# fuenteRegulada.net
KiCad netlist of a schematic drawn in Altium Designer
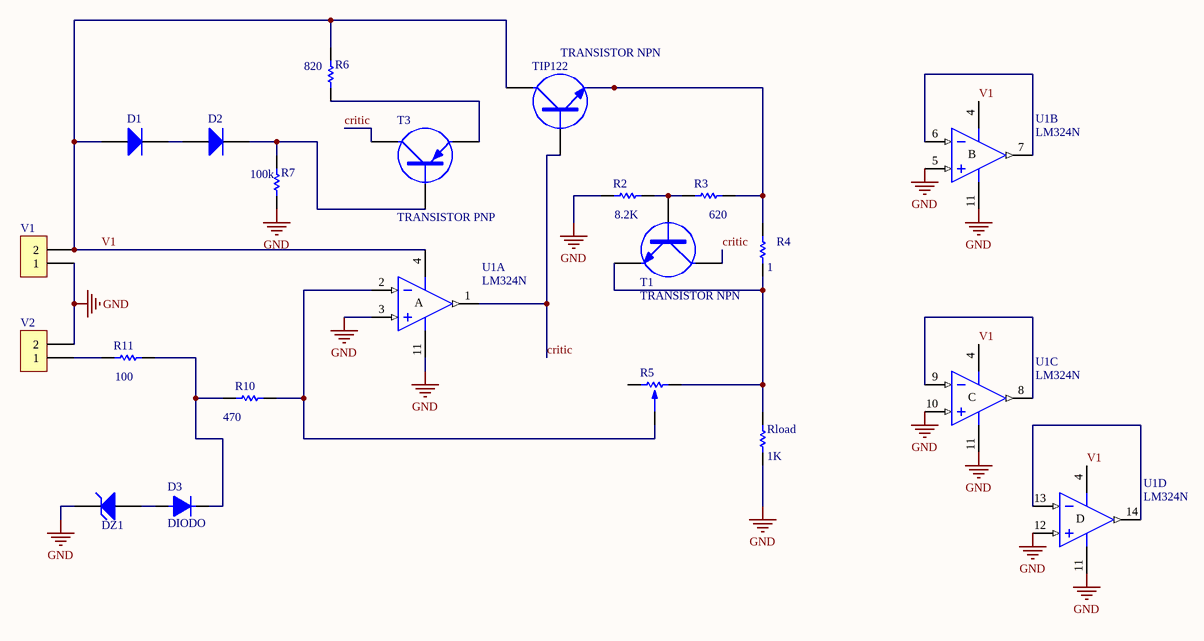
[diagram p0: fuenteRegulada.SchDoc]

(export (version "E")
  (design (tool "Eeschema 10.0.6"))
  (components
    (comp (ref "D1")
      (value "Diode 1N914")
      (footprint "DO-35")
      (description "High Conductance Fast Diode")
      (fields (field (name "PUBLISHER") "Altium Limited"))
      (libsource (lib "Miscellaneous Devices") (part "Diode 1N914"))
    )
    (comp (ref "D2")
      (value "Diode 1N914")
      (footprint "DO-35")
      (description "High Conductance Fast Diode")
      (fields (field (name "PUBLISHER") "Altium Limited"))
      (libsource (lib "Miscellaneous Devices") (part "Diode 1N914"))
    )
    (comp (ref "D3") (value "DIODO") (footprint "DO41") (libsource (lib "LIBEBAL") (part "DIODO")))
    (comp (ref "DZ1")
      (value "D Zener")
      (footprint "DIODE-0.7")
      (description "Zener Diode")
      (fields (field (name "PUBLISHER") "Altium Limited"))
      (libsource (lib "Miscellaneous Devices") (part "D Zener"))
    )
    (comp (ref "R2")
      (value "8.2K")
      (footprint "AXIAL-0.3")
      (description "Resistor")
      (fields (field (name "Comment") "Res1") (field (name "PUBLISHER") "Altium Limited"))
      (libsource (lib "Miscellaneous Devices") (part "Res1"))
    )
    (comp (ref "R3")
      (value "620")
      (footprint "AXIAL-0.3")
      (description "Resistor")
      (fields (field (name "Comment") "Res1") (field (name "PUBLISHER") "Altium Limited"))
      (libsource (lib "Miscellaneous Devices") (part "Res1"))
    )
    (comp (ref "R4")
      (value "1")
      (footprint "AXIAL-0.3")
      (description "Resistor")
      (fields (field (name "Comment") "Res1") (field (name "PUBLISHER") "Altium Limited"))
      (libsource (lib "Miscellaneous Devices") (part "Res1"))
    )
    (comp (ref "R5") (value "PRESET") (footprint "PRESET V") (libsource (lib "LIBEBAL") (part "PRESET")))
    (comp (ref "R6")
      (value "820")
      (footprint "AXIAL-0.3")
      (description "Resistor")
      (fields (field (name "Comment") "Res1") (field (name "PUBLISHER") "Altium Limited"))
      (libsource (lib "Miscellaneous Devices") (part "Res1"))
    )
    (comp (ref "R7")
      (value "100k")
      (footprint "AXIAL-0.3")
      (description "Resistor")
      (fields (field (name "Comment") "Res1") (field (name "PUBLISHER") "Altium Limited"))
      (libsource (lib "Miscellaneous Devices") (part "Res1"))
    )
    (comp (ref "R10")
      (value "470")
      (footprint "AXIAL-0.3")
      (description "Resistor")
      (fields (field (name "Comment") "Res1") (field (name "PUBLISHER") "Altium Limited"))
      (libsource (lib "Miscellaneous Devices") (part "Res1"))
    )
    (comp (ref "R11")
      (value "100")
      (footprint "AXIAL-0.3")
      (description "Resistor")
      (fields (field (name "Comment") "Res1") (field (name "PUBLISHER") "Altium Limited"))
      (libsource (lib "Miscellaneous Devices") (part "Res1"))
    )
    (comp (ref "Rload")
      (value "1K")
      (footprint "AXIAL-0.3")
      (description "Resistor")
      (fields (field (name "Comment") "Res1") (field (name "PUBLISHER") "Altium Limited"))
      (libsource (lib "Miscellaneous Devices") (part "Res1"))
    )
    (comp (ref "T1")
      (value "TRANSISTOR NPN")
      (footprint "TO92")
      (libsource (lib "LIBEBAL") (part "TRANSISTOR NPN"))
    )
    (comp (ref "T3")
      (value "TRANSISTOR PNP")
      (footprint "TO92")
      (libsource (lib "LIBEBAL") (part "TRANSISTOR PNP"))
    )
    (comp (ref "TIP122")
      (value "TRANSISTOR NPN")
      (footprint "TO-220 H")
      (libsource (lib "LIBEBAL") (part "TRANSISTOR NPN"))
    )
    (comp (ref "U1")
      (value "LM324N")
      (footprint "N014")
      (description "Quadruple Operational Amplifier")
      (fields (field (name "PUBLISHER") "Altium Limited"))
      (libsource (lib "TI Operational Amplifier") (part "LM324N"))
    )
    (comp (ref "V1")
      (value "BORNERA 2")
      (footprint "BORNERA2")
      (libsource (lib "LIBEBAL") (part "BORNERA 2"))
    )
    (comp (ref "V2")
      (value "BORNERA 2")
      (footprint "BORNERA2")
      (libsource (lib "LIBEBAL") (part "BORNERA 2"))
    )
  )
  (nets
    (net (code "1") (name "/V1") (class "Default")
      (node (ref "D1") (pin "1") (pinfunction "A_1") (pintype "passive"))
      (node (ref "R6") (pin "2") (pinfunction "2_2") (pintype "passive"))
      (node (ref "TIP122") (pin "2") (pinfunction "C_2") (pintype "passive"))
      (node (ref "U1") (pin "4") (pinfunction "V+_4") (pintype "power_in"))
      (node (ref "V1") (pin "2") (pinfunction "2_2") (pintype "passive"))
    )
    (net (code "2") (name "/critic") (class "Default")
      (node (ref "T1") (pin "2") (pinfunction "C_2") (pintype "passive"))
      (node (ref "T3") (pin "2") (pinfunction "C_2") (pintype "passive"))
      (node (ref "TIP122") (pin "1") (pinfunction "B_1") (pintype "passive"))
      (node (ref "U1") (pin "1") (pinfunction "OUT_1") (pintype "output"))
    )
    (net (code "3") (name "GND") (class "Default")
      (node (ref "DZ1") (pin "2") (pinfunction "K_2") (pintype "passive"))
      (node (ref "R2") (pin "2") (pinfunction "2_2") (pintype "passive"))
      (node (ref "R7") (pin "1") (pinfunction "1_1") (pintype "passive"))
      (node (ref "Rload") (pin "1") (pinfunction "1_1") (pintype "passive"))
      (node (ref "U1") (pin "10") (pinfunction "IN+_10") (pintype "input"))
      (node (ref "U1") (pin "11") (pinfunction "V-_11") (pintype "power_in"))
      (node (ref "U1") (pin "12") (pinfunction "IN+_12") (pintype "input"))
      (node (ref "U1") (pin "3") (pinfunction "IN+_3") (pintype "input"))
      (node (ref "U1") (pin "5") (pinfunction "IN+_5") (pintype "input"))
      (node (ref "V1") (pin "1") (pinfunction "1_1") (pintype "passive"))
      (node (ref "V2") (pin "2") (pinfunction "2_2") (pintype "passive"))
    )
    (net (code "4") (name "Net-(D1-K)") (class "Default")
      (node (ref "D1") (pin "2") (pinfunction "K_2") (pintype "passive"))
      (node (ref "D2") (pin "1") (pinfunction "A_1") (pintype "passive"))
    )
    (net (code "5") (name "Net-(D2-K)") (class "Default")
      (node (ref "D2") (pin "2") (pinfunction "K_2") (pintype "passive"))
      (node (ref "R7") (pin "2") (pinfunction "2_2") (pintype "passive"))
      (node (ref "T3") (pin "1") (pinfunction "B_1") (pintype "passive"))
    )
    (net (code "6") (name "Net-(D3-Pad2)") (class "Default")
      (node (ref "D3") (pin "2") (pinfunction "2_2") (pintype "passive"))
      (node (ref "R10") (pin "1") (pinfunction "1_1") (pintype "passive"))
      (node (ref "R11") (pin "2") (pinfunction "2_2") (pintype "passive"))
    )
    (net (code "7") (name "Net-(DZ1-A)") (class "Default")
      (node (ref "D3") (pin "1") (pinfunction "1_1") (pintype "passive"))
      (node (ref "DZ1") (pin "1") (pinfunction "A_1") (pintype "passive"))
    )
    (net (code "8") (name "Net-(R11-Pad1)") (class "Default")
      (node (ref "R11") (pin "1") (pinfunction "1_1") (pintype "passive"))
      (node (ref "V2") (pin "1") (pinfunction "1_1") (pintype "passive"))
    )
    (net (code "9") (name "Net-(T1-B)") (class "Default")
      (node (ref "R2") (pin "1") (pinfunction "1_1") (pintype "passive"))
      (node (ref "R3") (pin "2") (pinfunction "2_2") (pintype "passive"))
      (node (ref "T1") (pin "1") (pinfunction "B_1") (pintype "passive"))
    )
    (net (code "10") (name "Net-(T1-E)") (class "Default")
      (node (ref "R4") (pin "2") (pinfunction "2_2") (pintype "passive"))
      (node (ref "R5") (pin "1") (pinfunction "1_1") (pintype "passive"))
      (node (ref "Rload") (pin "2") (pinfunction "2_2") (pintype "passive"))
      (node (ref "T1") (pin "3") (pinfunction "E_3") (pintype "passive"))
    )
    (net (code "11") (name "Net-(T3-E)") (class "Default")
      (node (ref "R6") (pin "1") (pinfunction "1_1") (pintype "passive"))
      (node (ref "T3") (pin "3") (pinfunction "E_3") (pintype "passive"))
    )
    (net (code "12") (name "Net-(TIP122-E)") (class "Default")
      (node (ref "R3") (pin "1") (pinfunction "1_1") (pintype "passive"))
      (node (ref "R4") (pin "1") (pinfunction "1_1") (pintype "passive"))
      (node (ref "TIP122") (pin "3") (pinfunction "E_3") (pintype "passive"))
    )
    (net (code "13") (name "Net-(U1A-IN-)") (class "Default")
      (node (ref "R10") (pin "2") (pinfunction "2_2") (pintype "passive"))
      (node (ref "R5") (pin "2") (pinfunction "2_2") (pintype "passive"))
      (node (ref "U1") (pin "2") (pinfunction "IN-_2") (pintype "input"))
    )
    (net (code "14") (name "Net-(U1B-IN-)") (class "Default")
      (node (ref "U1") (pin "6") (pinfunction "IN-_6") (pintype "input"))
      (node (ref "U1") (pin "7") (pinfunction "OUT_7") (pintype "output"))
    )
    (net (code "15") (name "Net-(U1C-IN-)") (class "Default")
      (node (ref "U1") (pin "8") (pinfunction "OUT_8") (pintype "output"))
      (node (ref "U1") (pin "9") (pinfunction "IN-_9") (pintype "input"))
    )
    (net (code "16") (name "Net-(U1D-IN-)") (class "Default")
      (node (ref "U1") (pin "13") (pinfunction "IN-_13") (pintype "input"))
      (node (ref "U1") (pin "14") (pinfunction "OUT_14") (pintype "output"))
    )
    (net (code "17") (name "unconnected-(R5-Pad3)") (class "Default")
      (node (ref "R5") (pin "3") (pinfunction "3_3") (pintype "passive"))
    )
  )
)
